# cap-sensing.net
KiCad netlist of a schematic drawn in EAGLE
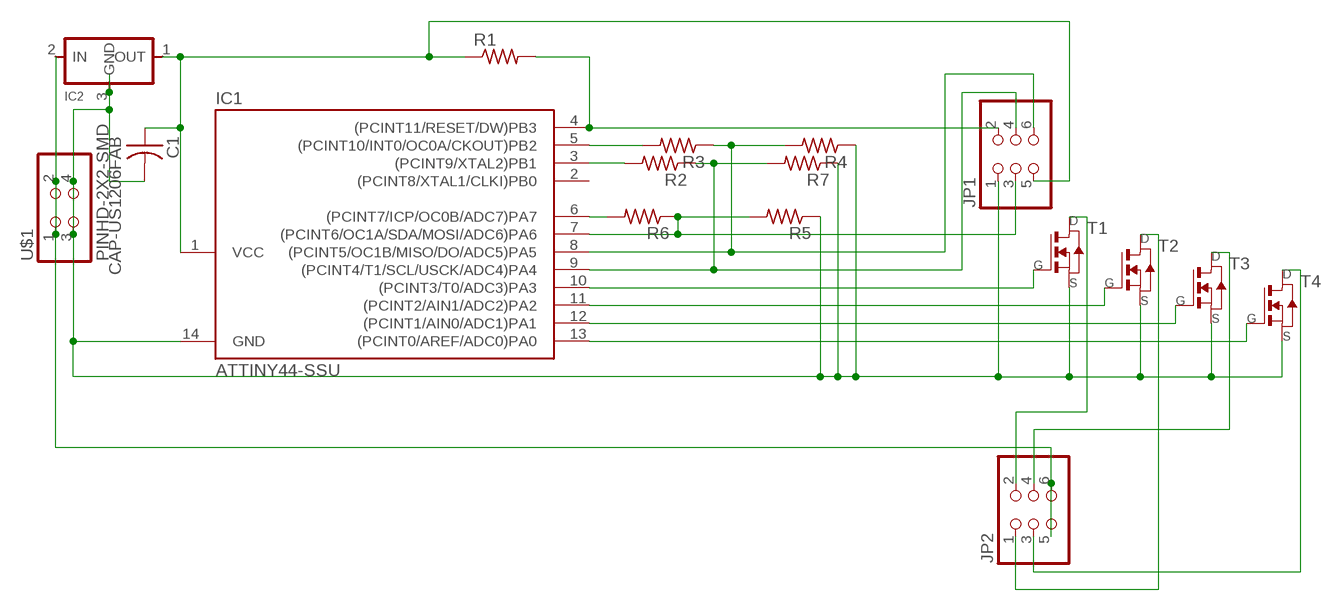
[diagram p0: schematic, sheet 1]

(export (version "E")
  (design (tool "Eeschema 10.0.6"))
  (components
    (comp (ref "C1")
      (value "CAP-US1206FAB")
      (footprint "eagle-import:C1206FAB")
      (libsource (lib "eagle-import") (part "CAP-US1206FAB"))
    )
    (comp (ref "IC1")
      (value "ATTINY44-SSU")
      (footprint "eagle-import:SOIC14")
      (libsource (lib "eagle-import") (part "ATTINY44-SSU"))
    )
    (comp (ref "IC2")
      (value "REGULATORSOT23")
      (footprint "eagle-import:SOT23")
      (libsource (lib "eagle-import") (part "REGULATORSOT23"))
    )
    (comp (ref "JP1")
      (value "PINHD-2X3-SMD")
      (footprint "eagle-import:2X03SMD")
      (libsource (lib "eagle-import") (part "PINHD-2X3-SMD"))
    )
    (comp (ref "JP2")
      (value "PINHD-2X3-SMD")
      (footprint "eagle-import:2X03SMD")
      (libsource (lib "eagle-import") (part "PINHD-2X3-SMD"))
    )
    (comp (ref "R1")
      (value "RES-US1206FAB")
      (footprint "eagle-import:R1206FAB")
      (libsource (lib "eagle-import") (part "RES-US1206FAB"))
    )
    (comp (ref "R2")
      (value "RES-US1206FAB")
      (footprint "eagle-import:R1206FAB")
      (libsource (lib "eagle-import") (part "RES-US1206FAB"))
    )
    (comp (ref "R3")
      (value "RES-US1206FAB")
      (footprint "eagle-import:R1206FAB")
      (libsource (lib "eagle-import") (part "RES-US1206FAB"))
    )
    (comp (ref "R4")
      (value "RES-US1206FAB")
      (footprint "eagle-import:R1206FAB")
      (libsource (lib "eagle-import") (part "RES-US1206FAB"))
    )
    (comp (ref "R5")
      (value "RES-US1206FAB")
      (footprint "eagle-import:R1206FAB")
      (libsource (lib "eagle-import") (part "RES-US1206FAB"))
    )
    (comp (ref "R6")
      (value "RES-US1206FAB")
      (footprint "eagle-import:R1206FAB")
      (libsource (lib "eagle-import") (part "RES-US1206FAB"))
    )
    (comp (ref "R7")
      (value "RES-US1206FAB")
      (footprint "eagle-import:R1206FAB")
      (libsource (lib "eagle-import") (part "RES-US1206FAB"))
    )
    (comp (ref "T1")
      (value "NMOSFETSOT23")
      (footprint "eagle-import:SOT-23")
      (libsource (lib "eagle-import") (part "NMOSFETSOT23"))
    )
    (comp (ref "T2")
      (value "NMOSFETSOT23")
      (footprint "eagle-import:SOT-23")
      (libsource (lib "eagle-import") (part "NMOSFETSOT23"))
    )
    (comp (ref "T3")
      (value "NMOSFETSOT23")
      (footprint "eagle-import:SOT-23")
      (libsource (lib "eagle-import") (part "NMOSFETSOT23"))
    )
    (comp (ref "T4")
      (value "NMOSFETSOT23")
      (footprint "eagle-import:SOT-23")
      (libsource (lib "eagle-import") (part "NMOSFETSOT23"))
    )
    (comp (ref "U$1")
      (value "PINHD-2X2-SMD")
      (footprint "eagle-import:2X02SMD")
      (libsource (lib "eagle-import") (part "PINHD-2X2-SMD"))
    )
  )
  (nets
    (net (code "1") (name "Net-(IC1-(PCINT0{slash}AREF{slash}ADC0)PA0)") (class "Default")
      (node (ref "IC1") (pin "13") (pinfunction "(PCINT0/AREF/ADC0)PA0_13") (pintype "bidirectional"))
      (node (ref "T4") (pin "3") (pinfunction "G_3") (pintype "passive"))
    )
    (net (code "2") (name "Net-(IC1-(PCINT1{slash}AIN0{slash}ADC1)PA1)") (class "Default")
      (node (ref "IC1") (pin "12") (pinfunction "(PCINT1/AIN0/ADC1)PA1_12") (pintype "bidirectional"))
      (node (ref "T3") (pin "3") (pinfunction "G_3") (pintype "passive"))
    )
    (net (code "3") (name "Net-(IC1-(PCINT2{slash}AIN1{slash}ADC2)PA2)") (class "Default")
      (node (ref "IC1") (pin "11") (pinfunction "(PCINT2/AIN1/ADC2)PA2_11") (pintype "bidirectional"))
      (node (ref "T2") (pin "3") (pinfunction "G_3") (pintype "passive"))
    )
    (net (code "4") (name "Net-(IC1-(PCINT3{slash}T0{slash}ADC3)PA3)") (class "Default")
      (node (ref "IC1") (pin "10") (pinfunction "(PCINT3/T0/ADC3)PA3_10") (pintype "bidirectional"))
      (node (ref "T1") (pin "3") (pinfunction "G_3") (pintype "passive"))
    )
    (net (code "5") (name "Net-(IC1-(PCINT4{slash}T1{slash}SCL{slash}USCK{slash}ADC4)PA4)") (class "Default")
      (node (ref "IC1") (pin "9") (pinfunction "(PCINT4/T1/SCL/USCK/ADC4)PA4_9") (pintype "bidirectional"))
      (node (ref "JP1") (pin "4") (pinfunction "4_4") (pintype "passive"))
      (node (ref "R2") (pin "1") (pinfunction "1_1") (pintype "passive"))
      (node (ref "R7") (pin "2") (pinfunction "2_2") (pintype "passive"))
    )
    (net (code "6") (name "Net-(IC1-(PCINT5{slash}OC1B{slash}MISO{slash}DO{slash}ADC5)PA5)") (class "Default")
      (node (ref "IC1") (pin "8") (pinfunction "(PCINT5/OC1B/MISO/DO/ADC5)PA5_8") (pintype "bidirectional"))
      (node (ref "JP1") (pin "6") (pinfunction "6_6") (pintype "passive"))
      (node (ref "R3") (pin "1") (pinfunction "1_1") (pintype "passive"))
      (node (ref "R4") (pin "2") (pinfunction "2_2") (pintype "passive"))
    )
    (net (code "7") (name "Net-(IC1-(PCINT6{slash}OC1A{slash}SDA{slash}MOSI{slash}ADC6)PA6)") (class "Default")
      (node (ref "IC1") (pin "7") (pinfunction "(PCINT6/OC1A/SDA/MOSI/ADC6)PA6_7") (pintype "bidirectional"))
      (node (ref "JP1") (pin "3") (pinfunction "3_3") (pintype "passive"))
      (node (ref "R5") (pin "2") (pinfunction "2_2") (pintype "passive"))
      (node (ref "R6") (pin "1") (pinfunction "1_1") (pintype "passive"))
    )
    (net (code "8") (name "Net-(IC1-(PCINT7{slash}ICP{slash}OC0B{slash}ADC7)PA7)") (class "Default")
      (node (ref "IC1") (pin "6") (pinfunction "(PCINT7/ICP/OC0B/ADC7)PA7_6") (pintype "bidirectional"))
      (node (ref "R6") (pin "2") (pinfunction "2_2") (pintype "passive"))
    )
    (net (code "9") (name "Net-(IC1-(PCINT9{slash}XTAL2)PB1)") (class "Default")
      (node (ref "IC1") (pin "3") (pinfunction "(PCINT9/XTAL2)PB1_3") (pintype "bidirectional"))
      (node (ref "R2") (pin "2") (pinfunction "2_2") (pintype "passive"))
    )
    (net (code "10") (name "Net-(IC1-(PCINT10{slash}INT0{slash}OC0A{slash}CKOUT)PB2)") (class "Default")
      (node (ref "IC1") (pin "5") (pinfunction "(PCINT10/INT0/OC0A/CKOUT)PB2_5") (pintype "bidirectional"))
      (node (ref "R3") (pin "2") (pinfunction "2_2") (pintype "passive"))
    )
    (net (code "11") (name "Net-(IC1-(PCINT11{slash}RESET{slash}DW)PB3)") (class "Default")
      (node (ref "IC1") (pin "4") (pinfunction "(PCINT11/RESET/DW)PB3_4") (pintype "bidirectional"))
      (node (ref "JP1") (pin "2") (pinfunction "2_2") (pintype "passive"))
      (node (ref "R1") (pin "2") (pinfunction "2_2") (pintype "passive"))
    )
    (net (code "12") (name "Net-(IC1-GND)") (class "Default")
      (node (ref "C1") (pin "2") (pinfunction "2_2") (pintype "passive"))
      (node (ref "IC1") (pin "14") (pinfunction "GND_14") (pintype "power_in"))
      (node (ref "IC2") (pin "3") (pinfunction "GND_3") (pintype "bidirectional"))
      (node (ref "JP1") (pin "1") (pinfunction "1_1") (pintype "passive"))
      (node (ref "R4") (pin "1") (pinfunction "1_1") (pintype "passive"))
      (node (ref "R5") (pin "1") (pinfunction "1_1") (pintype "passive"))
      (node (ref "R7") (pin "1") (pinfunction "1_1") (pintype "passive"))
      (node (ref "T1") (pin "2") (pinfunction "S_2") (pintype "passive"))
      (node (ref "T2") (pin "2") (pinfunction "S_2") (pintype "passive"))
      (node (ref "T3") (pin "2") (pinfunction "S_2") (pintype "passive"))
      (node (ref "T4") (pin "2") (pinfunction "S_2") (pintype "passive"))
      (node (ref "U$1") (pin "3") (pinfunction "3_3") (pintype "passive"))
      (node (ref "U$1") (pin "4") (pinfunction "4_4") (pintype "passive"))
    )
    (net (code "13") (name "Net-(IC1-VCC)") (class "Default")
      (node (ref "C1") (pin "1") (pinfunction "1_1") (pintype "passive"))
      (node (ref "IC1") (pin "1") (pinfunction "VCC_1") (pintype "power_in"))
      (node (ref "IC2") (pin "1") (pinfunction "OUT_1") (pintype "bidirectional"))
      (node (ref "JP1") (pin "5") (pinfunction "5_5") (pintype "passive"))
      (node (ref "R1") (pin "1") (pinfunction "1_1") (pintype "passive"))
    )
    (net (code "14") (name "Net-(IC2-IN)") (class "Default")
      (node (ref "IC2") (pin "2") (pinfunction "IN_2") (pintype "bidirectional"))
      (node (ref "JP2") (pin "5") (pinfunction "5_5") (pintype "passive"))
      (node (ref "JP2") (pin "6") (pinfunction "6_6") (pintype "passive"))
      (node (ref "U$1") (pin "1") (pinfunction "1_1") (pintype "passive"))
      (node (ref "U$1") (pin "2") (pinfunction "2_2") (pintype "passive"))
    )
    (net (code "15") (name "Net-(T1-D)") (class "Default")
      (node (ref "JP2") (pin "2") (pinfunction "2_2") (pintype "passive"))
      (node (ref "T1") (pin "1") (pinfunction "D_1") (pintype "passive"))
    )
    (net (code "16") (name "Net-(T2-D)") (class "Default")
      (node (ref "JP2") (pin "1") (pinfunction "1_1") (pintype "passive"))
      (node (ref "T2") (pin "1") (pinfunction "D_1") (pintype "passive"))
    )
    (net (code "17") (name "Net-(T3-D)") (class "Default")
      (node (ref "JP2") (pin "4") (pinfunction "4_4") (pintype "passive"))
      (node (ref "T3") (pin "1") (pinfunction "D_1") (pintype "passive"))
    )
    (net (code "18") (name "Net-(T4-D)") (class "Default")
      (node (ref "JP2") (pin "3") (pinfunction "3_3") (pintype "passive"))
      (node (ref "T4") (pin "1") (pinfunction "D_1") (pintype "passive"))
    )
    (net (code "19") (name "unconnected-(IC1-(PCINT8{slash}XTAL1{slash}CLKI)PB0-Pad2)") (class "Default")
      (node (ref "IC1") (pin "2") (pinfunction "(PCINT8/XTAL1/CLKI)PB0_2") (pintype "bidirectional"))
    )
  )
)
